# BRD161206.net
KiCad netlist of a schematic drawn in EAGLE
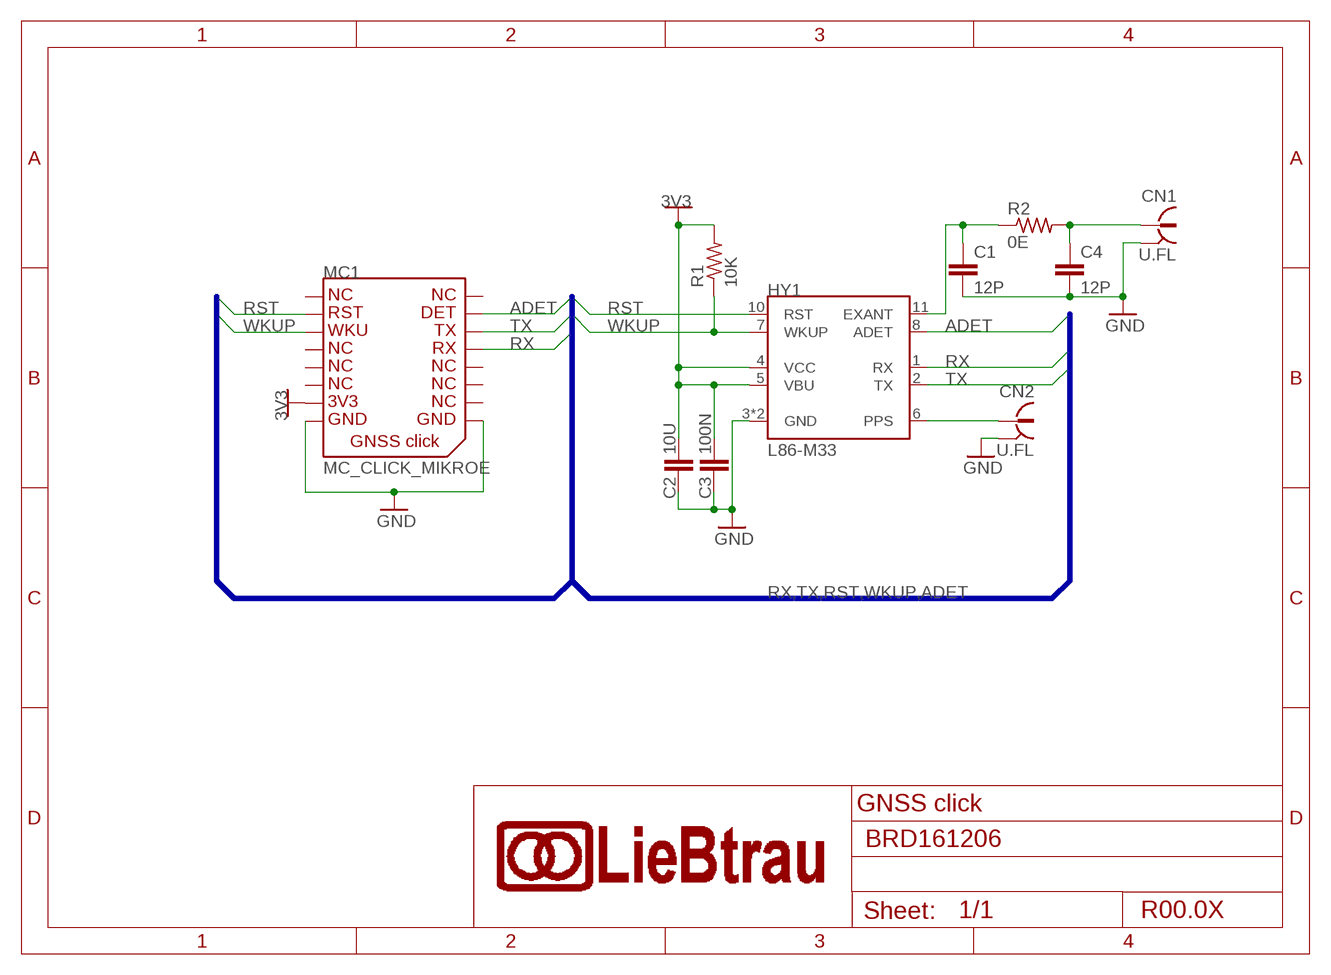
[diagram p0: schematic, sheet 1]

(export (version "E")
  (design (tool "Eeschema 10.0.6"))
  (components
    (comp (ref "C1")
      (value "12P")
      (footprint "eagle-import:CA_0603")
      (libsource (lib "eagle-import") (part "CA0603_12P_"))
    )
    (comp (ref "C2")
      (value "10U")
      (footprint "eagle-import:CA_1206")
      (libsource (lib "eagle-import") (part "CA1206_10U_"))
    )
    (comp (ref "C3")
      (value "100N")
      (footprint "eagle-import:CA_1206")
      (libsource (lib "eagle-import") (part "CA1206_100N_"))
    )
    (comp (ref "C4")
      (value "12P")
      (footprint "eagle-import:CA_0603")
      (libsource (lib "eagle-import") (part "CA0603_12P_"))
    )
    (comp (ref "CN1")
      (value "U.FL")
      (footprint "eagle-import:CN_RF_U.FL_MALE")
      (libsource (lib "eagle-import") (part "CN_COAXU.FL_MALE_UMC_IPEX_"))
    )
    (comp (ref "CN2")
      (value "U.FL")
      (footprint "eagle-import:CN_RF_U.FL_MALE")
      (libsource (lib "eagle-import") (part "CN_COAXU.FL_MALE_UMC_IPEX_"))
    )
    (comp (ref "HY1")
      (value "L86-M33")
      (footprint "eagle-import:HY_GNSS_L86-M33")
      (libsource (lib "eagle-import") (part "HY_GNSS_QUECTEL_L86-M33"))
    )
    (comp (ref "MC1")
      (value "MC_CLICK_MIKROE")
      (footprint "eagle-import:MC_CLICK_MIKROE")
      (fields
        (field (name "5V") "NC")
        (field (name "AN") "NC")
        (field (name "CS") "WKU")
        (field (name "INT") "DET")
        (field (name "MISO") "NC")
        (field (name "MOSI") "NC")
        (field (name "PWM") "NC")
        (field (name "SCK") "NC")
        (field (name "SCL") "NC")
        (field (name "SDA") "NC")
      )
      (libsource (lib "eagle-import") (part "MC_CLICK_MIKROE"))
    )
    (comp (ref "R1")
      (value "10K")
      (footprint "eagle-import:RE_1206")
      (libsource (lib "eagle-import") (part "RE1206_10K_"))
    )
    (comp (ref "R2")
      (value "0E")
      (footprint "eagle-import:RE_0603")
      (libsource (lib "eagle-import") (part "RE0603_0E_"))
    )
  )
  (nets
    (net (code "1") (name "/ADET") (class "Default")
      (node (ref "HY1") (pin "8") (pinfunction "ADET_8") (pintype "bidirectional"))
      (node (ref "MC1") (pin "P$15") (pinfunction "P$15_P$15") (pintype "bidirectional"))
    )
    (net (code "2") (name "/RST") (class "Default")
      (node (ref "HY1") (pin "10") (pinfunction "RST_10") (pintype "bidirectional"))
      (node (ref "MC1") (pin "P$2") (pinfunction "P$2_P$2") (pintype "bidirectional"))
    )
    (net (code "3") (name "/RX") (class "Default")
      (node (ref "HY1") (pin "1") (pinfunction "RX_1") (pintype "bidirectional"))
      (node (ref "MC1") (pin "P$13") (pinfunction "P$13_P$13") (pintype "bidirectional"))
    )
    (net (code "4") (name "/TX") (class "Default")
      (node (ref "HY1") (pin "2") (pinfunction "TX_2") (pintype "bidirectional"))
      (node (ref "MC1") (pin "P$14") (pinfunction "P$14_P$14") (pintype "bidirectional"))
    )
    (net (code "5") (name "/WKUP") (class "Default")
      (node (ref "HY1") (pin "7") (pinfunction "WKUP_7") (pintype "bidirectional"))
      (node (ref "MC1") (pin "P$3") (pinfunction "P$3_P$3") (pintype "bidirectional"))
      (node (ref "R1") (pin "1") (pinfunction "1_1") (pintype "passive"))
    )
    (net (code "7") (name "3V3") (class "Default")
      (node (ref "C2") (pin "1") (pinfunction "1_1") (pintype "passive"))
      (node (ref "C3") (pin "1") (pinfunction "1_1") (pintype "passive"))
      (node (ref "HY1") (pin "4") (pinfunction "VCC_4") (pintype "bidirectional"))
      (node (ref "HY1") (pin "5") (pinfunction "VBU_5") (pintype "bidirectional"))
      (node (ref "MC1") (pin "P$7") (pinfunction "P$7_P$7") (pintype "bidirectional"))
      (node (ref "R1") (pin "2") (pinfunction "2_2") (pintype "passive"))
    )
    (net (code "8") (name "GND") (class "Default")
      (node (ref "C1") (pin "2") (pinfunction "2_2") (pintype "passive"))
      (node (ref "C2") (pin "2") (pinfunction "2_2") (pintype "passive"))
      (node (ref "C3") (pin "2") (pinfunction "2_2") (pintype "passive"))
      (node (ref "C4") (pin "2") (pinfunction "2_2") (pintype "passive"))
      (node (ref "CN1") (pin "2A") (pinfunction "OUTER_2A") (pintype "passive"))
      (node (ref "CN1") (pin "2B") (pinfunction "OUTER_2B") (pintype "passive"))
      (node (ref "CN2") (pin "2A") (pinfunction "OUTER_2A") (pintype "passive"))
      (node (ref "CN2") (pin "2B") (pinfunction "OUTER_2B") (pintype "passive"))
      (node (ref "HY1") (pin "12") (pinfunction "GND_12") (pintype "bidirectional"))
      (node (ref "HY1") (pin "3") (pinfunction "GND_3") (pintype "bidirectional"))
      (node (ref "MC1") (pin "P$8") (pinfunction "8_P$8") (pintype "bidirectional"))
      (node (ref "MC1") (pin "P$9") (pinfunction "P$9_P$9") (pintype "bidirectional"))
    )
    (net (code "9") (name "Net-(CN1-INNER)") (class "Default")
      (node (ref "C4") (pin "1") (pinfunction "1_1") (pintype "passive"))
      (node (ref "CN1") (pin "1") (pinfunction "INNER_1") (pintype "passive"))
      (node (ref "R2") (pin "2") (pinfunction "2_2") (pintype "passive"))
    )
    (net (code "10") (name "Net-(CN2-INNER)") (class "Default")
      (node (ref "CN2") (pin "1") (pinfunction "INNER_1") (pintype "passive"))
      (node (ref "HY1") (pin "6") (pinfunction "PPS_6") (pintype "bidirectional"))
    )
    (net (code "11") (name "Net-(HY1-EXANT)") (class "Default")
      (node (ref "C1") (pin "1") (pinfunction "1_1") (pintype "passive"))
      (node (ref "HY1") (pin "11") (pinfunction "EXANT_11") (pintype "bidirectional"))
      (node (ref "R2") (pin "1") (pinfunction "1_1") (pintype "passive"))
    )
    (net (code "12") (name "unconnected-(MC1-PadP$1)") (class "Default")
      (node (ref "MC1") (pin "P$1") (pinfunction "P$1_P$1") (pintype "bidirectional"))
    )
    (net (code "13") (name "unconnected-(MC1-PadP$4)") (class "Default")
      (node (ref "MC1") (pin "P$4") (pinfunction "P$4_P$4") (pintype "bidirectional"))
    )
    (net (code "14") (name "unconnected-(MC1-PadP$5)") (class "Default")
      (node (ref "MC1") (pin "P$5") (pinfunction "P$5_P$5") (pintype "bidirectional"))
    )
    (net (code "15") (name "unconnected-(MC1-PadP$6)") (class "Default")
      (node (ref "MC1") (pin "P$6") (pinfunction "P$6_P$6") (pintype "bidirectional"))
    )
    (net (code "16") (name "unconnected-(MC1-PadP$10)") (class "Default")
      (node (ref "MC1") (pin "P$10") (pinfunction "P$10_P$10") (pintype "bidirectional"))
    )
    (net (code "17") (name "unconnected-(MC1-PadP$11)") (class "Default")
      (node (ref "MC1") (pin "P$11") (pinfunction "P$11_P$11") (pintype "bidirectional"))
    )
    (net (code "18") (name "unconnected-(MC1-PadP$12)") (class "Default")
      (node (ref "MC1") (pin "P$12") (pinfunction "P$12_P$12") (pintype "bidirectional"))
    )
    (net (code "19") (name "unconnected-(MC1-PadP$16)") (class "Default")
      (node (ref "MC1") (pin "P$16") (pinfunction "P$16_P$16") (pintype "bidirectional"))
    )
  )
)
